# WifiDongle.net
KiCad netlist of a schematic drawn in EAGLE
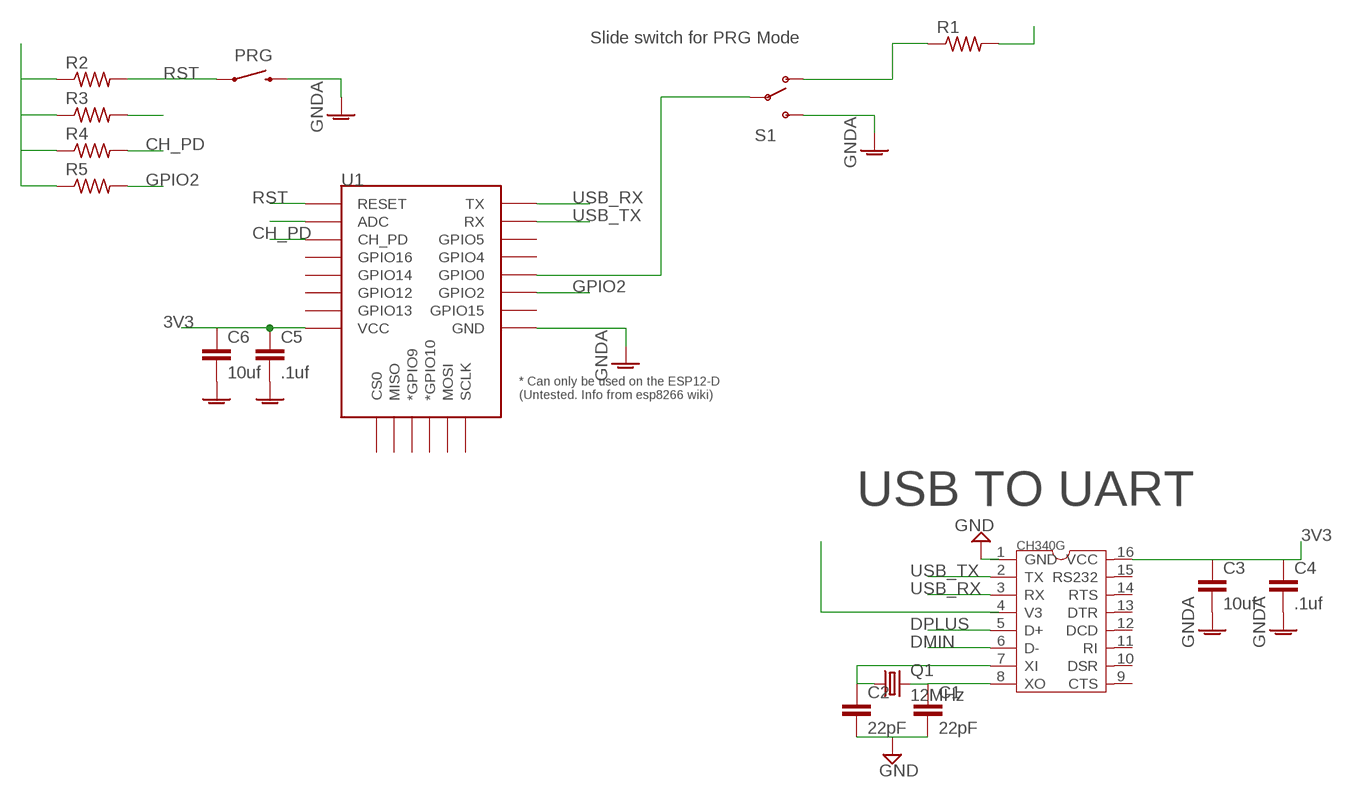
[diagram p0: schematic, sheet 1]

(export (version "E")
  (design (tool "Eeschema 10.0.6"))
  (components
    (comp (ref "C1")
      (value "22pF")
      (footprint "eagle-import:0603-CAP")
      (libsource (lib "eagle-import") (part "CAP0603-CAP"))
    )
    (comp (ref "C2")
      (value "22pF")
      (footprint "eagle-import:0603-CAP")
      (libsource (lib "eagle-import") (part "CAP0603-CAP"))
    )
    (comp (ref "C3")
      (value "10uf")
      (footprint "eagle-import:0603-CAP")
      (libsource (lib "eagle-import") (part "CAP0603-CAP"))
    )
    (comp (ref "C4")
      (value ".1uf")
      (footprint "eagle-import:0603-CAP")
      (libsource (lib "eagle-import") (part "CAP0603-CAP"))
    )
    (comp (ref "C5")
      (value ".1uf")
      (footprint "eagle-import:0603-CAP")
      (libsource (lib "eagle-import") (part "CAP0603-CAP"))
    )
    (comp (ref "C6")
      (value "10uf")
      (footprint "eagle-import:0603-CAP")
      (libsource (lib "eagle-import") (part "CAP0603-CAP"))
    )
    (comp (ref "CH340G")
      (value "CH340GCH340G")
      (footprint "eagle-import:SOP-16")
      (libsource (lib "eagle-import") (part "CH340GCH340G"))
    )
    (comp (ref "PRG")
      (value "SWITCH-MOMENTARY-2SMD-REDUNDANT")
      (footprint "eagle-import:TACTILE-SWITCH-SMD")
      (libsource (lib "eagle-import") (part "SWITCH-MOMENTARY-2SMD-REDUNDANT"))
    )
    (comp (ref "Q1")
      (value "12MHz")
      (footprint "eagle-import:HC49U70")
      (libsource (lib "eagle-import") (part "CRYSTALHC49U70"))
    )
    (comp (ref "R1")
      (value "R-US_R0603")
      (footprint "eagle-import:R0603")
      (libsource (lib "eagle-import") (part "R-US_R0603"))
    )
    (comp (ref "R2")
      (value "R-US_R0603")
      (footprint "eagle-import:R0603")
      (libsource (lib "eagle-import") (part "R-US_R0603"))
    )
    (comp (ref "R3")
      (value "R-US_R0603")
      (footprint "eagle-import:R0603")
      (libsource (lib "eagle-import") (part "R-US_R0603"))
    )
    (comp (ref "R4")
      (value "R-US_R0603")
      (footprint "eagle-import:R0603")
      (libsource (lib "eagle-import") (part "R-US_R0603"))
    )
    (comp (ref "R5")
      (value "R-US_R0603")
      (footprint "eagle-import:R0603")
      (libsource (lib "eagle-import") (part "R-US_R0603"))
    )
    (comp (ref "S1")
      (value "SWITCH-SPDT-SMD-A")
      (footprint "eagle-import:SWITCH-SPST-SMD-A")
      (libsource (lib "eagle-import") (part "SWITCH-SPDT-SMD-A"))
    )
    (comp (ref "U1")
      (value "ESP12ESMD")
      (footprint "eagle-import:ESP12E-SMD")
      (libsource (lib "eagle-import") (part "ESP12ESMD"))
    )
  )
  (nets
    (net (code "1") (name "/3V3") (class "Default")
      (node (ref "C3") (pin "1") (pinfunction "1_1") (pintype "passive"))
      (node (ref "C4") (pin "1") (pinfunction "1_1") (pintype "passive"))
      (node (ref "C5") (pin "1") (pinfunction "1_1") (pintype "passive"))
      (node (ref "C6") (pin "1") (pinfunction "1_1") (pintype "passive"))
      (node (ref "CH340G") (pin "16") (pinfunction "VCC_16") (pintype "output"))
      (node (ref "U1") (pin "VCC") (pinfunction "VCC_VCC") (pintype "bidirectional"))
    )
    (net (code "2") (name "/CH_PD") (class "Default")
      (node (ref "R4") (pin "2") (pinfunction "2_2") (pintype "passive"))
      (node (ref "U1") (pin "CH_PD") (pinfunction "CH_PD_CH_PD") (pintype "bidirectional"))
    )
    (net (code "3") (name "/DMIN") (class "Default")
      (node (ref "CH340G") (pin "6") (pinfunction "D-_6") (pintype "bidirectional"))
    )
    (net (code "4") (name "/DPLUS") (class "Default")
      (node (ref "CH340G") (pin "5") (pinfunction "D+_5") (pintype "bidirectional"))
    )
    (net (code "5") (name "/GPIO2") (class "Default")
      (node (ref "R5") (pin "2") (pinfunction "2_2") (pintype "passive"))
      (node (ref "U1") (pin "GPIO2") (pinfunction "GPIO2_GPIO2") (pintype "bidirectional"))
    )
    (net (code "6") (name "/RI") (class "Default")
      (node (ref "CH340G") (pin "11") (pinfunction "RI_11") (pintype "power_in"))
    )
    (net (code "7") (name "/RST") (class "Default")
      (node (ref "PRG") (pin "1") (pinfunction "1_1") (pintype "passive"))
      (node (ref "PRG") (pin "2") (pinfunction "1_2") (pintype "passive"))
      (node (ref "R2") (pin "2") (pinfunction "2_2") (pintype "passive"))
      (node (ref "U1") (pin "RESET") (pinfunction "RESET_RESET") (pintype "bidirectional"))
    )
    (net (code "8") (name "/USB_RX") (class "Default")
      (node (ref "CH340G") (pin "3") (pinfunction "RX_3") (pintype "bidirectional"))
      (node (ref "U1") (pin "TXD0") (pinfunction "TX_TXD0") (pintype "bidirectional"))
    )
    (net (code "9") (name "/USB_TX") (class "Default")
      (node (ref "CH340G") (pin "2") (pinfunction "TX_2") (pintype "bidirectional"))
      (node (ref "U1") (pin "RXD0") (pinfunction "RX_RXD0") (pintype "bidirectional"))
    )
    (net (code "10") (name "GND") (class "Default")
      (node (ref "C1") (pin "2") (pinfunction "2_2") (pintype "passive"))
      (node (ref "C2") (pin "2") (pinfunction "2_2") (pintype "passive"))
      (node (ref "CH340G") (pin "1") (pinfunction "GND_1") (pintype "bidirectional"))
    )
    (net (code "11") (name "GNDA") (class "Default")
      (node (ref "C3") (pin "2") (pinfunction "2_2") (pintype "passive"))
      (node (ref "C4") (pin "2") (pinfunction "2_2") (pintype "passive"))
      (node (ref "C5") (pin "2") (pinfunction "2_2") (pintype "passive"))
      (node (ref "C6") (pin "2") (pinfunction "2_2") (pintype "passive"))
      (node (ref "PRG") (pin "3") (pinfunction "2_3") (pintype "passive"))
      (node (ref "PRG") (pin "4") (pinfunction "2_4") (pintype "passive"))
      (node (ref "S1") (pin "3") (pinfunction "S_3") (pintype "passive"))
      (node (ref "U1") (pin "GND") (pinfunction "GND_GND") (pintype "bidirectional"))
    )
    (net (code "12") (name "Net-(CH340G-XI)") (class "Default")
      (node (ref "C2") (pin "1") (pinfunction "1_1") (pintype "passive"))
      (node (ref "CH340G") (pin "7") (pinfunction "XI_7") (pintype "power_in"))
      (node (ref "Q1") (pin "1") (pinfunction "1_1") (pintype "passive"))
    )
    (net (code "13") (name "Net-(CH340G-XO)") (class "Default")
      (node (ref "C1") (pin "1") (pinfunction "1_1") (pintype "passive"))
      (node (ref "CH340G") (pin "8") (pinfunction "XO_8") (pintype "input"))
      (node (ref "Q1") (pin "2") (pinfunction "2_2") (pintype "passive"))
    )
    (net (code "14") (name "Net-(R2-Pad1)") (class "Default")
      (node (ref "R2") (pin "1") (pinfunction "1_1") (pintype "passive"))
      (node (ref "R3") (pin "1") (pinfunction "1_1") (pintype "passive"))
      (node (ref "R4") (pin "1") (pinfunction "1_1") (pintype "passive"))
      (node (ref "R5") (pin "1") (pinfunction "1_1") (pintype "passive"))
    )
    (net (code "15") (name "Net-(S1-O)") (class "Default")
      (node (ref "R1") (pin "1") (pinfunction "1_1") (pintype "passive"))
      (node (ref "S1") (pin "1") (pinfunction "O_1") (pintype "passive"))
    )
    (net (code "16") (name "Net-(S1-P)") (class "Default")
      (node (ref "S1") (pin "2") (pinfunction "P_2") (pintype "passive"))
      (node (ref "U1") (pin "GPIO0") (pinfunction "GPIO0_GPIO0") (pintype "bidirectional"))
    )
    (net (code "17") (name "unconnected-(CH340G-CTS-Pad9)") (class "Default")
      (node (ref "CH340G") (pin "9") (pinfunction "CTS_9") (pintype "bidirectional"))
    )
    (net (code "18") (name "unconnected-(CH340G-DCD-Pad12)") (class "Default")
      (node (ref "CH340G") (pin "12") (pinfunction "DCD_12") (pintype "output"))
    )
    (net (code "19") (name "unconnected-(CH340G-DSR-Pad10)") (class "Default")
      (node (ref "CH340G") (pin "10") (pinfunction "DSR_10") (pintype "bidirectional"))
    )
    (net (code "20") (name "unconnected-(CH340G-DTR-Pad13)") (class "Default")
      (node (ref "CH340G") (pin "13") (pinfunction "DTR_13") (pintype "input"))
    )
    (net (code "21") (name "unconnected-(CH340G-RS232-Pad15)") (class "Default")
      (node (ref "CH340G") (pin "15") (pinfunction "RS232_15") (pintype "input"))
    )
    (net (code "22") (name "unconnected-(CH340G-RTS-Pad14)") (class "Default")
      (node (ref "CH340G") (pin "14") (pinfunction "RTS_14") (pintype "input"))
    )
    (net (code "23") (name "unconnected-(CH340G-V3-Pad4)") (class "Default")
      (node (ref "CH340G") (pin "4") (pinfunction "V3_4") (pintype "bidirectional"))
    )
    (net (code "24") (name "unconnected-(R1-Pad2)") (class "Default")
      (node (ref "R1") (pin "2") (pinfunction "2_2") (pintype "passive"))
    )
    (net (code "25") (name "unconnected-(R3-Pad2)") (class "Default")
      (node (ref "R3") (pin "2") (pinfunction "2_2") (pintype "passive"))
    )
    (net (code "26") (name "unconnected-(U1-*GPIO9-PadGPIO9)") (class "Default")
      (node (ref "U1") (pin "GPIO9") (pinfunction "*GPIO9_GPIO9") (pintype "bidirectional"))
    )
    (net (code "27") (name "unconnected-(U1-*GPIO10-PadGPIO10)") (class "Default")
      (node (ref "U1") (pin "GPIO10") (pinfunction "*GPIO10_GPIO10") (pintype "bidirectional"))
    )
    (net (code "28") (name "unconnected-(U1-PadADC)") (class "Default")
      (node (ref "U1") (pin "ADC") (pinfunction "ADC_ADC") (pintype "bidirectional"))
    )
    (net (code "29") (name "unconnected-(U1-PadCS0)") (class "Default")
      (node (ref "U1") (pin "CS0") (pinfunction "CS0_CS0") (pintype "bidirectional"))
    )
    (net (code "30") (name "unconnected-(U1-PadGPIO4)") (class "Default")
      (node (ref "U1") (pin "GPIO4") (pinfunction "GPIO4_GPIO4") (pintype "bidirectional"))
    )
    (net (code "31") (name "unconnected-(U1-PadGPIO5)") (class "Default")
      (node (ref "U1") (pin "GPIO5") (pinfunction "GPIO5_GPIO5") (pintype "bidirectional"))
    )
    (net (code "32") (name "unconnected-(U1-PadGPIO12)") (class "Default")
      (node (ref "U1") (pin "GPIO12") (pinfunction "GPIO12_GPIO12") (pintype "bidirectional"))
    )
    (net (code "33") (name "unconnected-(U1-PadGPIO13)") (class "Default")
      (node (ref "U1") (pin "GPIO13") (pinfunction "GPIO13_GPIO13") (pintype "bidirectional"))
    )
    (net (code "34") (name "unconnected-(U1-PadGPIO14)") (class "Default")
      (node (ref "U1") (pin "GPIO14") (pinfunction "GPIO14_GPIO14") (pintype "bidirectional"))
    )
    (net (code "35") (name "unconnected-(U1-PadGPIO15)") (class "Default")
      (node (ref "U1") (pin "GPIO15") (pinfunction "GPIO15_GPIO15") (pintype "bidirectional"))
    )
    (net (code "36") (name "unconnected-(U1-PadGPIO16)") (class "Default")
      (node (ref "U1") (pin "GPIO16") (pinfunction "GPIO16_GPIO16") (pintype "bidirectional"))
    )
    (net (code "37") (name "unconnected-(U1-PadMISO)") (class "Default")
      (node (ref "U1") (pin "MISO") (pinfunction "MISO_MISO") (pintype "bidirectional"))
    )
    (net (code "38") (name "unconnected-(U1-PadMOSI)") (class "Default")
      (node (ref "U1") (pin "MOSI") (pinfunction "MOSI_MOSI") (pintype "bidirectional"))
    )
    (net (code "39") (name "unconnected-(U1-PadSCLK)") (class "Default")
      (node (ref "U1") (pin "SCLK") (pinfunction "SCLK_SCLK") (pintype "bidirectional"))
    )
  )
)
